# 2025.net
KiCad netlist of a schematic drawn in Altium Designer
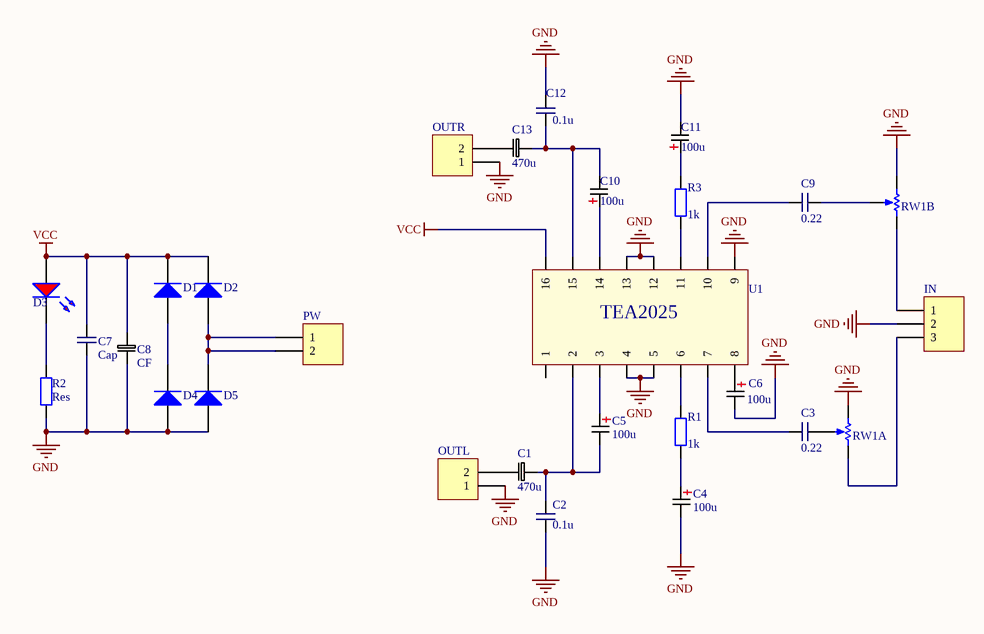
[diagram p0: 2025.SchDoc]

(export (version "E")
  (design (tool "Eeschema 10.0.6"))
  (components
    (comp (ref "C1") (value "470u") (footprint "CF0.1-6.5") (libsource (lib "MY") (part "CF")))
    (comp (ref "C2") (value "0.1u") (footprint "RAD0.1") (libsource (lib "MY") (part "Cap")))
    (comp (ref "C3") (value "0.22") (footprint "RAD-0.2") (libsource (lib "MY") (part "Cap")))
    (comp (ref "C4") (value "100u") (footprint "CF0.1") (libsource (lib "MY") (part "Cap Pol")))
    (comp (ref "C5") (value "100u") (footprint "CF0.1") (libsource (lib "MY") (part "Cap Pol")))
    (comp (ref "C6") (value "100u") (footprint "CF0.1") (libsource (lib "MY") (part "Cap Pol")))
    (comp (ref "C7") (value "Cap") (footprint "RAD0.1") (libsource (lib "MY") (part "Cap")))
    (comp (ref "C8") (value "CF") (footprint "CF0.2-13") (libsource (lib "MY") (part "CF")))
    (comp (ref "C9") (value "0.22") (footprint "RAD-0.2") (libsource (lib "MY") (part "Cap")))
    (comp (ref "C10") (value "100u") (footprint "CF0.1") (libsource (lib "MY") (part "Cap Pol")))
    (comp (ref "C11") (value "100u") (footprint "CF0.1") (libsource (lib "MY") (part "Cap Pol")))
    (comp (ref "C12") (value "0.1u") (footprint "RAD0.1") (libsource (lib "MY") (part "Cap")))
    (comp (ref "C13") (value "470u") (footprint "CF0.1-6.5") (libsource (lib "MY") (part "CF")))
    (comp (ref "D1")
      (value "Diode 1N4007")
      (footprint "DIO10.46-5.3x2.8")
      (description "1 Amp General Purpose Rectifier")
      (fields (field (name "PUBLISHER") "Altium Limited"))
      (libsource (lib "Miscellaneous Devices") (part "Diode 1N4007"))
    )
    (comp (ref "D2")
      (value "Diode 1N4007")
      (footprint "DIO10.46-5.3x2.8")
      (description "1 Amp General Purpose Rectifier")
      (fields (field (name "PUBLISHER") "Altium Limited"))
      (libsource (lib "Miscellaneous Devices") (part "Diode 1N4007"))
    )
    (comp (ref "D3")
      (value "LED0")
      (footprint "LED")
      (fields (field (name "PUBLISHER") "Altium Limited"))
      (libsource (lib "MY") (part "LED0"))
    )
    (comp (ref "D4")
      (value "Diode 1N4007")
      (footprint "DIO10.46-5.3x2.8")
      (description "1 Amp General Purpose Rectifier")
      (fields (field (name "PUBLISHER") "Altium Limited"))
      (libsource (lib "Miscellaneous Devices") (part "Diode 1N4007"))
    )
    (comp (ref "D5")
      (value "Diode 1N4007")
      (footprint "DIO10.46-5.3x2.8")
      (description "1 Amp General Purpose Rectifier")
      (fields (field (name "PUBLISHER") "Altium Limited"))
      (libsource (lib "Miscellaneous Devices") (part "Diode 1N4007"))
    )
    (comp (ref "IN")
      (value "~")
      (footprint "HDR1X3")
      (description "Header, 3-Pin, Right Angle")
      (fields (field (name "PUBLISHER") "Altium Limited"))
      (libsource (lib "Miscellaneous Connectors") (part "Header 3H"))
    )
    (comp (ref "OUTL")
      (value "Header 2")
      (footprint "HDR1X2")
      (description "Header, 2-Pin")
      (fields (field (name "PUBLISHER") "Altium Limited"))
      (libsource (lib "") (part "Header 2_1"))
    )
    (comp (ref "OUTR")
      (value "Header 2")
      (footprint "HDR1X2")
      (description "Header, 2-Pin")
      (fields (field (name "PUBLISHER") "Altium Limited"))
      (libsource (lib "") (part "Header 2_1"))
    )
    (comp (ref "PW")
      (value "Header 2")
      (footprint "HDR1X2")
      (description "Header, 2-Pin")
      (fields (field (name "PUBLISHER") "Altium Limited"))
      (libsource (lib "Miscellaneous Connectors") (part "Header 2"))
    )
    (comp (ref "R1")
      (value "1k")
      (footprint "RAD-0.1")
      (description "Resistor")
      (fields (field (name "PUBLISHER") "Altium Limited"))
      (libsource (lib "MY") (part "Res"))
    )
    (comp (ref "R2")
      (value "Res")
      (footprint "RAD0.1")
      (description "Resistor")
      (fields (field (name "PUBLISHER") "Altium Limited"))
      (libsource (lib "") (part "Res_1"))
    )
    (comp (ref "R3")
      (value "1k")
      (footprint "RAD0.1")
      (description "Resistor")
      (fields (field (name "PUBLISHER") "Altium Limited"))
      (libsource (lib "MY") (part "Res"))
    )
    (comp (ref "RW1") (value "RW") (footprint "RW") (libsource (lib "MY") (part "RW")))
    (comp (ref "U1") (value "TEA2025") (footprint "DIP16") (libsource (lib "MY") (part "TEA2025")))
  )
  (nets
    (net (code "1") (name "GND") (class "Default")
      (node (ref "C11") (pin "2") (pinfunction "2_2") (pintype "passive"))
      (node (ref "C12") (pin "1") (pinfunction "1_1") (pintype "passive"))
      (node (ref "C2") (pin "2") (pinfunction "2_2") (pintype "passive"))
      (node (ref "C4") (pin "2") (pinfunction "2_2") (pintype "passive"))
      (node (ref "C6") (pin "2") (pinfunction "2_2") (pintype "passive"))
      (node (ref "C7") (pin "1") (pinfunction "1_1") (pintype "passive"))
      (node (ref "C8") (pin "2") (pinfunction "2_2") (pintype "passive"))
      (node (ref "D4") (pin "1") (pinfunction "A_1") (pintype "passive"))
      (node (ref "D5") (pin "1") (pinfunction "A_1") (pintype "passive"))
      (node (ref "IN") (pin "2") (pinfunction "2_2") (pintype "passive"))
      (node (ref "OUTL") (pin "1") (pinfunction "1_1") (pintype "passive"))
      (node (ref "OUTR") (pin "1") (pinfunction "1_1") (pintype "passive"))
      (node (ref "R2") (pin "1") (pinfunction "1_1") (pintype "passive"))
      (node (ref "RW1") (pin "1") (pinfunction "TOP_1") (pintype "passive"))
      (node (ref "RW1") (pin "4") (pinfunction "TOP_4") (pintype "passive"))
      (node (ref "U1") (pin "12") (pinfunction "12_12") (pintype "passive"))
      (node (ref "U1") (pin "13") (pinfunction "13_13") (pintype "passive"))
      (node (ref "U1") (pin "4") (pinfunction "4_4") (pintype "passive"))
      (node (ref "U1") (pin "5") (pinfunction "5_5") (pintype "passive"))
      (node (ref "U1") (pin "9") (pinfunction "9_9") (pintype "passive"))
    )
    (net (code "2") (name "Net-(C1-Pad1)") (class "Default")
      (node (ref "C1") (pin "1") (pinfunction "1_1") (pintype "passive"))
      (node (ref "C2") (pin "1") (pinfunction "1_1") (pintype "passive"))
      (node (ref "C5") (pin "2") (pinfunction "2_2") (pintype "passive"))
      (node (ref "U1") (pin "2") (pinfunction "2_2") (pintype "passive"))
    )
    (net (code "3") (name "Net-(C1-Pad2)") (class "Default")
      (node (ref "C1") (pin "2") (pinfunction "2_2") (pintype "passive"))
      (node (ref "OUTL") (pin "2") (pinfunction "2_2") (pintype "passive"))
    )
    (net (code "4") (name "Net-(C3-Pad2)") (class "Default")
      (node (ref "C3") (pin "2") (pinfunction "2_2") (pintype "passive"))
      (node (ref "U1") (pin "7") (pinfunction "7_7") (pintype "passive"))
    )
    (net (code "5") (name "Net-(C4-Pad1)") (class "Default")
      (node (ref "C4") (pin "1") (pinfunction "1_1") (pintype "passive"))
      (node (ref "R1") (pin "2") (pinfunction "2_2") (pintype "passive"))
    )
    (net (code "6") (name "Net-(C5-Pad1)") (class "Default")
      (node (ref "C5") (pin "1") (pinfunction "1_1") (pintype "passive"))
      (node (ref "U1") (pin "3") (pinfunction "3_3") (pintype "passive"))
    )
    (net (code "7") (name "Net-(C6-Pad1)") (class "Default")
      (node (ref "C6") (pin "1") (pinfunction "1_1") (pintype "passive"))
      (node (ref "U1") (pin "8") (pinfunction "8_8") (pintype "passive"))
    )
    (net (code "8") (name "Net-(C9-Pad2)") (class "Default")
      (node (ref "C9") (pin "2") (pinfunction "2_2") (pintype "passive"))
      (node (ref "U1") (pin "10") (pinfunction "10_10") (pintype "passive"))
    )
    (net (code "9") (name "Net-(C10-Pad1)") (class "Default")
      (node (ref "C10") (pin "1") (pinfunction "1_1") (pintype "passive"))
      (node (ref "U1") (pin "14") (pinfunction "14_14") (pintype "passive"))
    )
    (net (code "10") (name "Net-(C10-Pad2)") (class "Default")
      (node (ref "C10") (pin "2") (pinfunction "2_2") (pintype "passive"))
      (node (ref "C12") (pin "2") (pinfunction "2_2") (pintype "passive"))
      (node (ref "C13") (pin "1") (pinfunction "1_1") (pintype "passive"))
      (node (ref "U1") (pin "15") (pinfunction "15_15") (pintype "passive"))
    )
    (net (code "11") (name "Net-(C11-Pad1)") (class "Default")
      (node (ref "C11") (pin "1") (pinfunction "1_1") (pintype "passive"))
      (node (ref "R3") (pin "1") (pinfunction "1_1") (pintype "passive"))
    )
    (net (code "12") (name "Net-(C13-Pad2)") (class "Default")
      (node (ref "C13") (pin "2") (pinfunction "2_2") (pintype "passive"))
      (node (ref "OUTR") (pin "2") (pinfunction "2_2") (pintype "passive"))
    )
    (net (code "13") (name "Net-(D1-A)") (class "Default")
      (node (ref "D1") (pin "1") (pinfunction "A_1") (pintype "passive"))
      (node (ref "D4") (pin "2") (pinfunction "K_2") (pintype "passive"))
    )
    (net (code "14") (name "Net-(D2-A)") (class "Default")
      (node (ref "D2") (pin "1") (pinfunction "A_1") (pintype "passive"))
      (node (ref "D5") (pin "2") (pinfunction "K_2") (pintype "passive"))
      (node (ref "PW") (pin "1") (pinfunction "1_1") (pintype "passive"))
      (node (ref "PW") (pin "2") (pinfunction "2_2") (pintype "passive"))
    )
    (net (code "15") (name "Net-(D3-K)") (class "Default")
      (node (ref "D3") (pin "2") (pinfunction "K_2") (pintype "passive"))
      (node (ref "R2") (pin "2") (pinfunction "2_2") (pintype "passive"))
    )
    (net (code "16") (name "Net-(R1-Pad1)") (class "Default")
      (node (ref "R1") (pin "1") (pinfunction "1_1") (pintype "passive"))
      (node (ref "U1") (pin "6") (pinfunction "6_6") (pintype "passive"))
    )
    (net (code "17") (name "Net-(R3-Pad2)") (class "Default")
      (node (ref "R3") (pin "2") (pinfunction "2_2") (pintype "passive"))
      (node (ref "U1") (pin "11") (pinfunction "11_11") (pintype "passive"))
    )
    (net (code "18") (name "Net-(RW1A-BOT)") (class "Default")
      (node (ref "IN") (pin "3") (pinfunction "3_3") (pintype "passive"))
      (node (ref "RW1") (pin "3") (pinfunction "BOT_3") (pintype "passive"))
    )
    (net (code "19") (name "Net-(RW1A-TAP)") (class "Default")
      (node (ref "C3") (pin "1") (pinfunction "1_1") (pintype "passive"))
      (node (ref "RW1") (pin "2") (pinfunction "TAP_2") (pintype "passive"))
    )
    (net (code "20") (name "Net-(RW1B-BOT)") (class "Default")
      (node (ref "IN") (pin "1") (pinfunction "1_1") (pintype "passive"))
      (node (ref "RW1") (pin "6") (pinfunction "BOT_6") (pintype "passive"))
    )
    (net (code "21") (name "Net-(RW1B-TAP)") (class "Default")
      (node (ref "C9") (pin "1") (pinfunction "1_1") (pintype "passive"))
      (node (ref "RW1") (pin "5") (pinfunction "TAP_5") (pintype "passive"))
    )
    (net (code "22") (name "VCC") (class "Default")
      (node (ref "C7") (pin "2") (pinfunction "2_2") (pintype "passive"))
      (node (ref "C8") (pin "1") (pinfunction "1_1") (pintype "passive"))
      (node (ref "D1") (pin "2") (pinfunction "K_2") (pintype "passive"))
      (node (ref "D2") (pin "2") (pinfunction "K_2") (pintype "passive"))
      (node (ref "D3") (pin "1") (pinfunction "A_1") (pintype "passive"))
      (node (ref "U1") (pin "16") (pinfunction "16_16") (pintype "passive"))
    )
    (net (code "23") (name "unconnected-(U1-Pad1)") (class "Default")
      (node (ref "U1") (pin "1") (pinfunction "1_1") (pintype "passive"))
    )
  )
)
